# rtc.net
KiCad netlist of a schematic drawn in Altium Designer
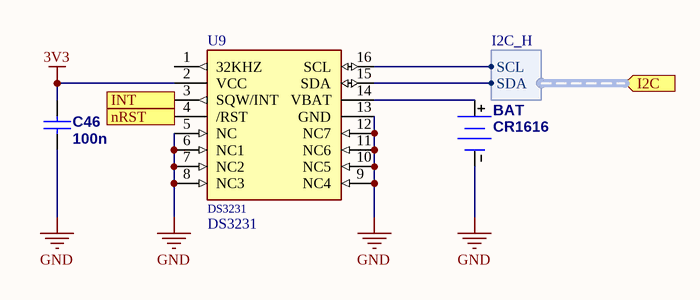
[diagram p0: rtc.SchDoc]

(export (version "E")
  (design (tool "Eeschema 10.0.6"))
  (components
    (comp (ref "BAT")
      (value "CR1616")
      (footprint "KEYSTONE_3016")
      (description "CR1616 Battery")
      (fields (field (name "PUBLISHER") "Altium Limited"))
      (libsource (lib "baterries_and_accus") (part "CR1616 Battery"))
    )
    (comp (ref "C46")
      (value "100n")
      (footprint "C0603")
      (description "Capacitor")
      (libsource (lib "capacitors") (part "Cap"))
    )
    (comp (ref "U9")
      (value "DS3231")
      (footprint "SO16W")
      (description "å®žæ—¶æ—¶é’Ÿï¼ˆRTCï¼‰ICæ—¶é’Ÿ/æ—¥åŽ†IÂ²Cï¼Œ2çº¿ä¸²è¡Œ16-SOICï¼ˆ0.295â€œï¼Œ7.50mmå®½åº¦ï¼‰")
      (fields (field (name "MF") "Maxim Integrated"))
      (libsource (lib "DS3231") (part "DS3231"))
    )
  )
  (nets
    (net (code "2") (name "/INT") (class "Default")
      (node (ref "U9") (pin "3") (pinfunction "SQW/INT_3") (pintype "output"))
    )
    (net (code "3") (name "/SCL") (class "Default")
      (node (ref "U9") (pin "16") (pinfunction "SCL_16") (pintype "bidirectional"))
    )
    (net (code "4") (name "/SDA") (class "Default")
      (node (ref "U9") (pin "15") (pinfunction "SDA_15") (pintype "bidirectional"))
    )
    (net (code "5") (name "/nRST") (class "Default")
      (node (ref "U9") (pin "4") (pinfunction "/RST_4") (pintype "passive"))
    )
    (net (code "7") (name "3V3") (class "Default")
      (node (ref "C46") (pin "2") (pinfunction "2_2") (pintype "passive"))
      (node (ref "U9") (pin "2") (pinfunction "VCC_2") (pintype "power_in"))
    )
    (net (code "8") (name "GND") (class "Default")
      (node (ref "BAT") (pin "2") (pinfunction "-_2") (pintype "passive"))
      (node (ref "C46") (pin "1") (pinfunction "1_1") (pintype "passive"))
      (node (ref "U9") (pin "10") (pinfunction "NC5_10") (pintype "input"))
      (node (ref "U9") (pin "11") (pinfunction "NC6_11") (pintype "input"))
      (node (ref "U9") (pin "12") (pinfunction "NC7_12") (pintype "input"))
      (node (ref "U9") (pin "13") (pinfunction "GND_13") (pintype "power_in"))
      (node (ref "U9") (pin "5") (pinfunction "NC_5") (pintype "input"))
      (node (ref "U9") (pin "6") (pinfunction "NC1_6") (pintype "input"))
      (node (ref "U9") (pin "7") (pinfunction "NC2_7") (pintype "input"))
      (node (ref "U9") (pin "8") (pinfunction "NC3_8") (pintype "input"))
      (node (ref "U9") (pin "9") (pinfunction "NC4_9") (pintype "input"))
    )
    (net (code "9") (name "Net-(BAT-+)") (class "Default")
      (node (ref "BAT") (pin "1") (pinfunction "+_1") (pintype "passive"))
      (node (ref "U9") (pin "14") (pinfunction "VBAT_14") (pintype "power_in"))
    )
    (net (code "10") (name "unconnected-(U9-32KHZ-Pad1)") (class "Default")
      (node (ref "U9") (pin "1") (pinfunction "32KHZ_1") (pintype "output"))
    )
  )
)
